# SDCard.net
KiCad netlist of a schematic drawn in Altium Designer
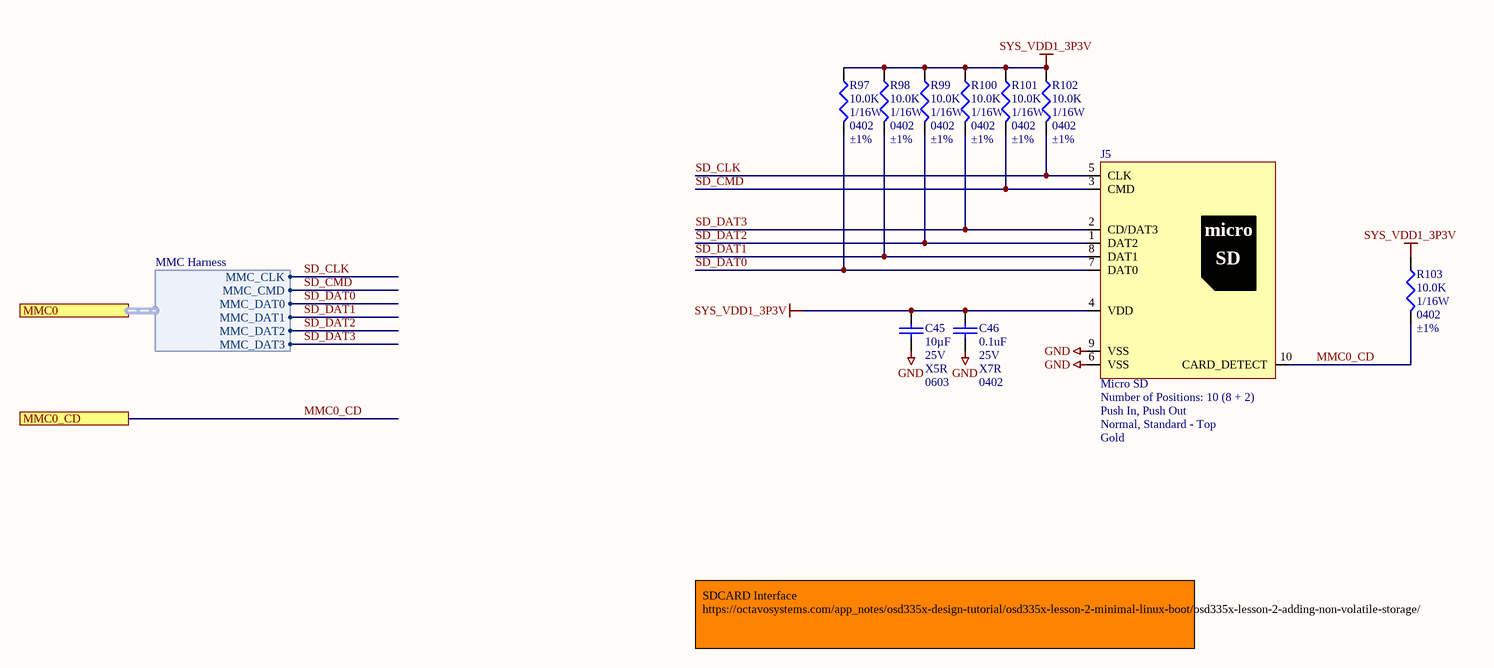
[diagram p0: SDCard.SchDoc]

(export (version "E")
  (design (tool "Eeschema 10.0.6"))
  (components
    (comp (ref "C45")
      (value "C_0603_10µF")
      (footprint "C_ERA-0603")
      (description "CAP CER 10UF 16V X5R 0603")
      (fields
        (field (name "CAPACITANCE") "10µF")
        (field (name "VOLTAGE - RATED") "25V")
        (field (name "TEMPERATURE COEFFICIENT") "X5R")
        (field (name "PACKAGE / CASE") "0603")
        (field (name "MANUFACTURER") "Murata Electronics North America")
        (field (name "MANUFACTURER PART NUMBER") "GRM188R61C106MA73D")
      )
      (libsource (lib "Cospan Design") (part "C_0603_10µF"))
    )
    (comp (ref "C46")
      (value "C_0402_0.1UF_25V")
      (footprint "C_0402")
      (description "CAP CER 0.1UF 25V X6S 0402")
      (fields
        (field (name "TOLERANCE") "10%")
        (field (name "CAPACITANCE") "0.1uF")
        (field (name "VOLTAGE - RATED") "25V")
        (field (name "TEMPERATURE COEFFICIENT") "X7R")
        (field (name "PACKAGE / CASE") "0402")
      )
      (libsource (lib "Cospan Design") (part "C_0402_0.1UF_25V"))
    )
    (comp (ref "J5")
      (value "Micro SD")
      (footprint "MICRO SD")
      (description "CONN MICRO SD R/A PUSH-PUSH SMD")
      (fields
        (field (name "MANUFACTURER") "Molex Inc")
        (field (name "MANUFACTURER PART NUMBER") "502570-0893")
        (field (name "NUMBER OF POSITIONS") "10 (8 + 2)")
        (field (name "INSERTION, REMOVAL METHOD") "Push In, Push Out")
        (field (name "MOUNTING FEATURE") "Normal, Standard - Top")
        (field (name "CONTACT FINISH") "Gold")
      )
      (libsource (lib "Main Library") (part "J_MICRO_SD"))
    )
    (comp (ref "R97")
      (value "R_0402_10.0K")
      (footprint "R_0402")
      (description "RES 10.0K OHM 1/16W 1% 0402 SMD")
      (fields
        (field (name "MANUFACTURER") "Stackpole Electronics Inc")
        (field (name "MANUFACTURER PART NUMBER") "RMCF0402FT10K0")
        (field (name "RESISTANCE IN OHMS") "10.0K")
        (field (name "POWER (WATTS)") "1/16W")
        (field (name "CASE") "0402")
        (field (name "TOLERANCE") "±1%")
      )
      (libsource (lib "Main Library") (part "R_0402_10.0K"))
    )
    (comp (ref "R98")
      (value "R_0402_10.0K")
      (footprint "R_0402")
      (description "RES 10.0K OHM 1/16W 1% 0402 SMD")
      (fields
        (field (name "MANUFACTURER") "Stackpole Electronics Inc")
        (field (name "MANUFACTURER PART NUMBER") "RMCF0402FT10K0")
        (field (name "RESISTANCE IN OHMS") "10.0K")
        (field (name "POWER (WATTS)") "1/16W")
        (field (name "CASE") "0402")
        (field (name "TOLERANCE") "±1%")
      )
      (libsource (lib "Main Library") (part "R_0402_10.0K"))
    )
    (comp (ref "R99")
      (value "R_0402_10.0K")
      (footprint "R_0402")
      (description "RES 10.0K OHM 1/16W 1% 0402 SMD")
      (fields
        (field (name "MANUFACTURER") "Stackpole Electronics Inc")
        (field (name "MANUFACTURER PART NUMBER") "RMCF0402FT10K0")
        (field (name "RESISTANCE IN OHMS") "10.0K")
        (field (name "POWER (WATTS)") "1/16W")
        (field (name "CASE") "0402")
        (field (name "TOLERANCE") "±1%")
      )
      (libsource (lib "Main Library") (part "R_0402_10.0K"))
    )
    (comp (ref "R100")
      (value "R_0402_10.0K")
      (footprint "R_0402")
      (description "RES 10.0K OHM 1/16W 1% 0402 SMD")
      (fields
        (field (name "MANUFACTURER") "Stackpole Electronics Inc")
        (field (name "MANUFACTURER PART NUMBER") "RMCF0402FT10K0")
        (field (name "RESISTANCE IN OHMS") "10.0K")
        (field (name "POWER (WATTS)") "1/16W")
        (field (name "CASE") "0402")
        (field (name "TOLERANCE") "±1%")
      )
      (libsource (lib "Main Library") (part "R_0402_10.0K"))
    )
    (comp (ref "R101")
      (value "R_0402_10.0K")
      (footprint "R_0402")
      (description "RES 10.0K OHM 1/16W 1% 0402 SMD")
      (fields
        (field (name "MANUFACTURER") "Stackpole Electronics Inc")
        (field (name "MANUFACTURER PART NUMBER") "RMCF0402FT10K0")
        (field (name "RESISTANCE IN OHMS") "10.0K")
        (field (name "POWER (WATTS)") "1/16W")
        (field (name "CASE") "0402")
        (field (name "TOLERANCE") "±1%")
      )
      (libsource (lib "Main Library") (part "R_0402_10.0K"))
    )
    (comp (ref "R102")
      (value "R_0402_10.0K")
      (footprint "R_0402")
      (description "RES 10.0K OHM 1/16W 1% 0402 SMD")
      (fields
        (field (name "MANUFACTURER") "Stackpole Electronics Inc")
        (field (name "MANUFACTURER PART NUMBER") "RMCF0402FT10K0")
        (field (name "RESISTANCE IN OHMS") "10.0K")
        (field (name "POWER (WATTS)") "1/16W")
        (field (name "CASE") "0402")
        (field (name "TOLERANCE") "±1%")
      )
      (libsource (lib "Main Library") (part "R_0402_10.0K"))
    )
    (comp (ref "R103")
      (value "R_0402_10.0K")
      (footprint "R_0402")
      (description "RES 10.0K OHM 1/16W 1% 0402 SMD")
      (fields
        (field (name "MANUFACTURER") "Stackpole Electronics Inc")
        (field (name "MANUFACTURER PART NUMBER") "RMCF0402FT10K0")
        (field (name "RESISTANCE IN OHMS") "10.0K")
        (field (name "POWER (WATTS)") "1/16W")
        (field (name "CASE") "0402")
        (field (name "TOLERANCE") "±1%")
      )
      (libsource (lib "Main Library") (part "R_0402_10.0K"))
    )
  )
  (nets
    (net (code "3") (name "/MMC0_CD") (class "Default")
      (node (ref "J5") (pin "10") (pinfunction "CARD_DETECT_10") (pintype "passive"))
      (node (ref "R103") (pin "2") (pinfunction "2_2") (pintype "passive"))
    )
    (net (code "4") (name "/SD_CLK") (class "Default")
      (node (ref "J5") (pin "5") (pinfunction "CLK_5") (pintype "passive"))
      (node (ref "R102") (pin "2") (pinfunction "2_2") (pintype "passive"))
    )
    (net (code "5") (name "/SD_CMD") (class "Default")
      (node (ref "J5") (pin "3") (pinfunction "CMD_3") (pintype "passive"))
      (node (ref "R101") (pin "2") (pinfunction "2_2") (pintype "passive"))
    )
    (net (code "6") (name "/SD_DAT0") (class "Default")
      (node (ref "J5") (pin "7") (pinfunction "DAT0_7") (pintype "passive"))
      (node (ref "R97") (pin "2") (pinfunction "2_2") (pintype "passive"))
    )
    (net (code "7") (name "/SD_DAT1") (class "Default")
      (node (ref "J5") (pin "8") (pinfunction "DAT1_8") (pintype "passive"))
      (node (ref "R98") (pin "2") (pinfunction "2_2") (pintype "passive"))
    )
    (net (code "8") (name "/SD_DAT2") (class "Default")
      (node (ref "J5") (pin "1") (pinfunction "DAT2_1") (pintype "passive"))
      (node (ref "R99") (pin "2") (pinfunction "2_2") (pintype "passive"))
    )
    (net (code "9") (name "/SD_DAT3") (class "Default")
      (node (ref "J5") (pin "2") (pinfunction "CD/DAT3_2") (pintype "passive"))
      (node (ref "R100") (pin "2") (pinfunction "2_2") (pintype "passive"))
    )
    (net (code "11") (name "GND") (class "Default")
      (node (ref "C45") (pin "1") (pinfunction "1_1") (pintype "passive"))
      (node (ref "C46") (pin "1") (pinfunction "1_1") (pintype "passive"))
      (node (ref "J5") (pin "6") (pinfunction "VSS_6") (pintype "passive"))
      (node (ref "J5") (pin "9") (pinfunction "VSS_9") (pintype "passive"))
    )
    (net (code "12") (name "SYS_VDD1_3P3V") (class "Default")
      (node (ref "C45") (pin "2") (pinfunction "2_2") (pintype "passive"))
      (node (ref "C46") (pin "2") (pinfunction "2_2") (pintype "passive"))
      (node (ref "J5") (pin "4") (pinfunction "VDD_4") (pintype "passive"))
      (node (ref "R100") (pin "1") (pinfunction "1_1") (pintype "passive"))
      (node (ref "R101") (pin "1") (pinfunction "1_1") (pintype "passive"))
      (node (ref "R102") (pin "1") (pinfunction "1_1") (pintype "passive"))
      (node (ref "R103") (pin "1") (pinfunction "1_1") (pintype "passive"))
      (node (ref "R97") (pin "1") (pinfunction "1_1") (pintype "passive"))
      (node (ref "R98") (pin "1") (pinfunction "1_1") (pintype "passive"))
      (node (ref "R99") (pin "1") (pinfunction "1_1") (pintype "passive"))
    )
  )
)
